# CC2538_MCU.net
KiCad netlist of a schematic drawn in Altium Designer
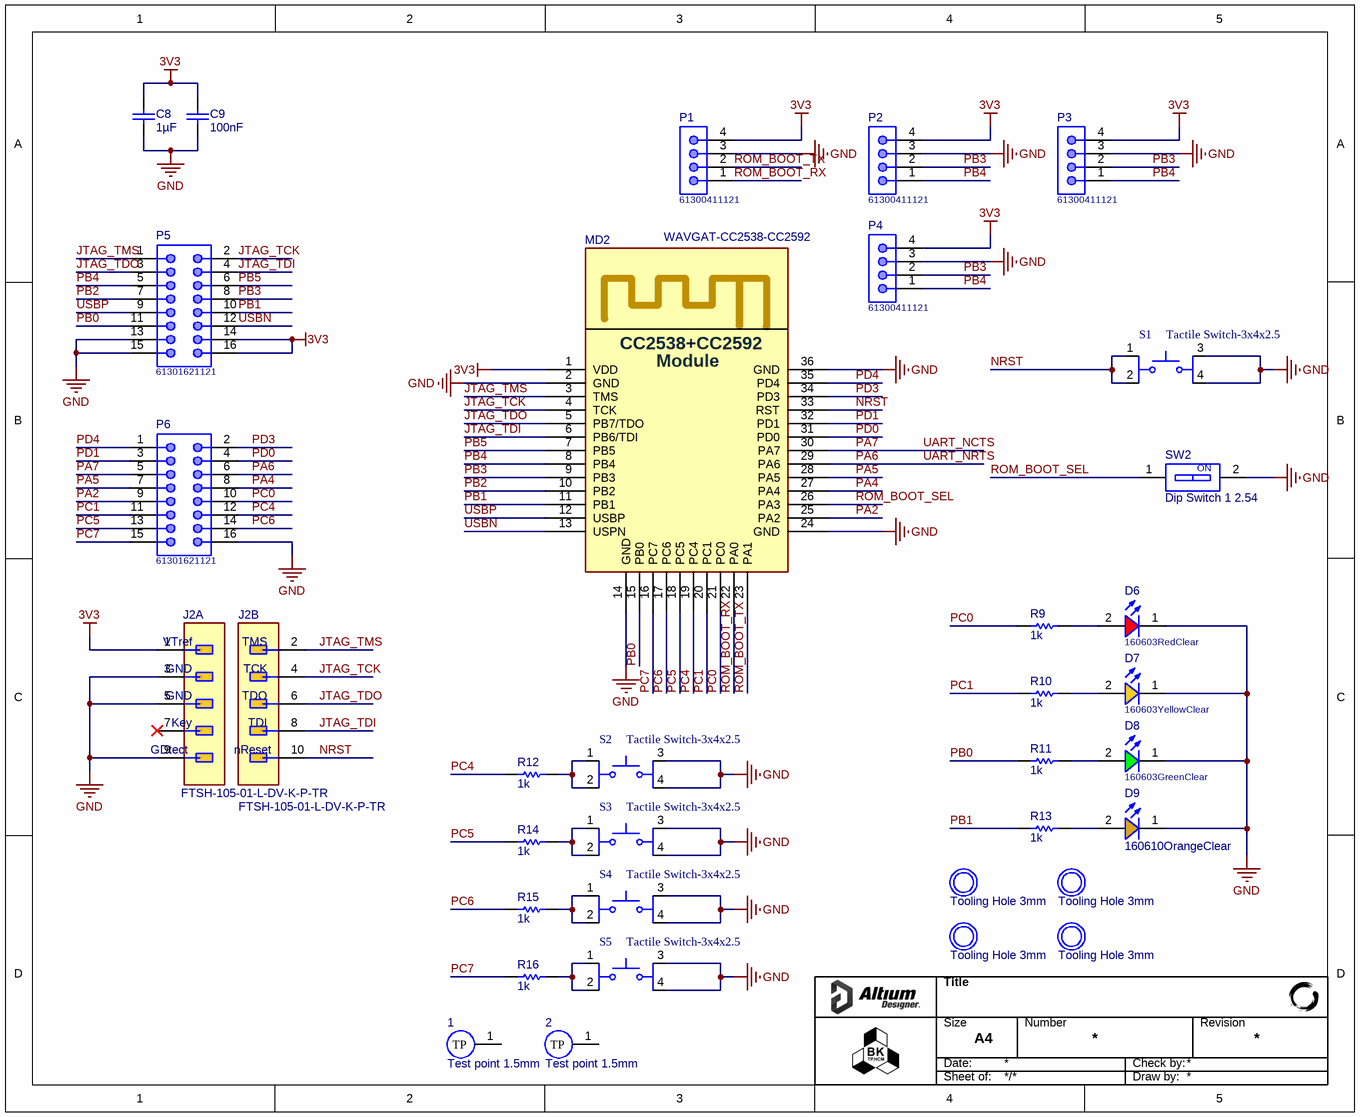
[diagram p0: [CC2538] MCU.SchDoc]

(export (version "E")
  (design (tool "Eeschema 10.0.6"))
  (components
    (comp (ref "1")
      (value "Test point 1.5mm")
      (footprint "Test point 1.5mm-Footprint-1")
      (description "Test point, 1.5mm radius")
      (libsource (lib "University of Technology") (part "TP"))
    )
    (comp (ref "2")
      (value "Test point 1.5mm")
      (footprint "Test point 1.5mm-Footprint-1")
      (description "Test point, 1.5mm radius")
      (libsource (lib "University of Technology") (part "TP"))
    )
    (comp (ref "C8")
      (value "1µF")
      (footprint "CAP_0603")
      (description "CAP, size 0603, 1 uF, 16 VDC, 10%")
      (fields
        (field (name "MANUFACTURER PART NUMBER") "CL10B105KO8NNWC")
        (field (name "TOLERANCE") "10%")
        (field (name "SOURCE") "Capacitor_0603_10_percent.SchLib")
      )
      (libsource (lib "University of Technology") (part "010603475106.3"))
    )
    (comp (ref "C9")
      (value "100nF")
      (footprint "CAP_0603")
      (description "CAP, size 0603, 100 nF, 50 VDC, 10%")
      (fields
        (field (name "MANUFACTURER PART NUMBER") "CGA3E3X8R1H104K080AE")
        (field (name "LCSC PART #") "C14663")
        (field (name "SOURCE") "Capacitor_0603_10_percent.SchLib")
      )
      (libsource (lib "University of Technology") (part "010603475106.3"))
    )
    (comp (ref "D6")
      (value "160603RedClear")
      (footprint "WL-SMCW_0603_H=0.7mm")
      (description "WL-SMCW SMT Mono-color Chip LED Waterclear, size 0603, Red, 2V, 140deg")
      (libsource (lib "University of Technology") (part "160603RedClear"))
    )
    (comp (ref "D7")
      (value "160603YellowClear")
      (footprint "WL-SMCW_0603_H=0.7mm")
      (description "WL-SMCW SMT Mono-color Chip LED Waterclear, size 0603, Yellow, 2V, 140deg")
      (libsource (lib "University of Technology") (part "160603YellowClear"))
    )
    (comp (ref "D8")
      (value "160603GreenClear")
      (footprint "WL-SMCW_0603_H=0.7mm")
      (description "WL-SMCW SMT Mono-color Chip LED Waterclear, size 0603, Green, 3.2V, 140deg")
      (libsource (lib "University of Technology") (part "160603GreenClear"))
    )
    (comp (ref "D9")
      (value "160610OrangeClear")
      (footprint "WL-SMCW_0603_H=0.7mm")
      (libsource (lib "University of Technology") (part "160610OrangeClear"))
    )
    (comp (ref "H1")
      (value "Tooling Hole 3mm")
      (footprint "3mm")
      (libsource (lib "University of Technology") (part "Tooling Hole 5mm"))
    )
    (comp (ref "H2")
      (value "Tooling Hole 3mm")
      (footprint "3mm")
      (libsource (lib "University of Technology") (part "Tooling Hole 5mm"))
    )
    (comp (ref "H3")
      (value "Tooling Hole 3mm")
      (footprint "3mm")
      (libsource (lib "University of Technology") (part "Tooling Hole 5mm"))
    )
    (comp (ref "H4")
      (value "Tooling Hole 3mm")
      (footprint "3mm")
      (libsource (lib "University of Technology") (part "Tooling Hole 5mm"))
    )
    (comp (ref "J2")
      (value "FTSH-105-01-L-DV-K-P-TR")
      (footprint "FP-FTSH-105-01-L-DV-K-P-T-MFG")
      (libsource (lib "University of Technology") (part "544f42128f4185dcb88ce1ce9bf1982"))
    )
    (comp (ref "MD2")
      (value "WAVGAT-CC2538-CC2592")
      (footprint "WAVGAT-CC2538-CC2592-Footprint")
      (description "WAVGAT-CC2538-CC2592 Module")
      (libsource (lib "University of Technology") (part "WAVGAT-CC2538-CC2592-Symbol"))
    )
    (comp (ref "P1")
      (value "61300411121")
      (footprint "61300411121")
      (description "WR-PHD Pin Header, THT, pitch 2.54mm, Single Row, Vertical, 4p")
      (fields (field (name "MANUFACTURER") "Wurth Elektronik"))
      (libsource (lib "University of Technology") (part "61300411121"))
    )
    (comp (ref "P2")
      (value "61300411121")
      (footprint "61300411121")
      (description "WR-PHD Pin Header, THT, pitch 2.54mm, Single Row, Vertical, 4p")
      (fields (field (name "MANUFACTURER") "Wurth Elektronik"))
      (libsource (lib "University of Technology") (part "61300411121"))
    )
    (comp (ref "P3")
      (value "61300411121")
      (footprint "61300411121")
      (description "WR-PHD Pin Header, THT, pitch 2.54mm, Single Row, Vertical, 4p")
      (fields (field (name "MANUFACTURER") "Wurth Elektronik"))
      (libsource (lib "University of Technology") (part "61300411121"))
    )
    (comp (ref "P4")
      (value "61300411121")
      (footprint "61300411121")
      (description "WR-PHD Pin Header, THT, pitch 2.54mm, Single Row, Vertical, 4p")
      (fields (field (name "MANUFACTURER") "Wurth Elektronik"))
      (libsource (lib "University of Technology") (part "61300411121"))
    )
    (comp (ref "P5")
      (value "61301621121")
      (footprint "61301621121")
      (description "WR-PHD Pin Header, THT, pitch 2.54mm, Dual Row, Vertical, 16p")
      (fields (field (name "MANUFACTURER") "Wurth Elektronik"))
      (libsource (lib "University of Technology") (part "61301621121"))
    )
    (comp (ref "P6")
      (value "61301621121")
      (footprint "61301621121")
      (description "WR-PHD Pin Header, THT, pitch 2.54mm, Dual Row, Vertical, 16p")
      (fields (field (name "MANUFACTURER") "Wurth Elektronik"))
      (libsource (lib "University of Technology") (part "61301621121"))
    )
    (comp (ref "R9")
      (value "1k")
      (footprint "RES_0603")
      (description "RES, size 0603, 1 KOhm, 1/10 W, 1%")
      (fields (field (name "TOLERANCE") "1%") (field (name "MANUFACTURER PART NUMBER") "RC0603FR-071KL"))
      (libsource (lib "University of Technology") (part "00060371541"))
    )
    (comp (ref "R10")
      (value "1k")
      (footprint "RES_0603")
      (description "RES, size 0603, 1 KOhm, 1/10 W, 1%")
      (fields (field (name "TOLERANCE") "1%") (field (name "MANUFACTURER PART NUMBER") "RC0603FR-071KL"))
      (libsource (lib "University of Technology") (part "00060371541"))
    )
    (comp (ref "R11")
      (value "1k")
      (footprint "RES_0603")
      (description "RES, size 0603, 1 KOhm, 1/10 W, 1%")
      (fields (field (name "TOLERANCE") "1%") (field (name "MANUFACTURER PART NUMBER") "RC0603FR-071KL"))
      (libsource (lib "University of Technology") (part "00060371541"))
    )
    (comp (ref "R12")
      (value "1k")
      (footprint "RES_0603")
      (description "RES, size 0603, 1 KOhm, 1/10 W, 5%")
      (fields (field (name "TOLERANCE") "5%") (field (name "MANUFACTURER PART NUMBER") "ERJ-UP3J102V"))
      (libsource (lib "University of Technology") (part "00060371541"))
    )
    (comp (ref "R13")
      (value "1k")
      (footprint "RES_0603")
      (description "RES, size 0603, 1 KOhm, 1/10 W, 1%")
      (fields (field (name "TOLERANCE") "1%") (field (name "MANUFACTURER PART NUMBER") "RC0603FR-071KL"))
      (libsource (lib "University of Technology") (part "00060371541"))
    )
    (comp (ref "R14")
      (value "1k")
      (footprint "RES_0603")
      (description "RES, size 0603, 1 KOhm, 1/10 W, 5%")
      (fields (field (name "TOLERANCE") "5%") (field (name "MANUFACTURER PART NUMBER") "ERJ-UP3J102V"))
      (libsource (lib "University of Technology") (part "00060371541"))
    )
    (comp (ref "R15")
      (value "1k")
      (footprint "RES_0603")
      (description "RES, size 0603, 1 KOhm, 1/10 W, 5%")
      (fields (field (name "TOLERANCE") "5%") (field (name "MANUFACTURER PART NUMBER") "ERJ-UP3J102V"))
      (libsource (lib "University of Technology") (part "00060371541"))
    )
    (comp (ref "R16")
      (value "1k")
      (footprint "RES_0603")
      (description "RES, size 0603, 1 KOhm, 1/10 W, 5%")
      (fields (field (name "TOLERANCE") "5%") (field (name "MANUFACTURER PART NUMBER") "ERJ-UP3J102V"))
      (libsource (lib "University of Technology") (part "00060371541"))
    )
    (comp (ref "S1")
      (value "Tactile Switch-3x4x2.5")
      (footprint "Tactile Switch-3x4x2.5 Footprint")
      (description "Tactile Switch, 3x4x2.5mm")
      (libsource (lib "University of Technology") (part "Tactile Switch"))
    )
    (comp (ref "S2")
      (value "Tactile Switch-3x4x2.5")
      (footprint "Tactile Switch-3x4x2.5 Footprint")
      (description "Tactile Switch, 3x4x2.5mm")
      (libsource (lib "University of Technology") (part "Tactile Switch"))
    )
    (comp (ref "S3")
      (value "Tactile Switch-3x4x2.5")
      (footprint "Tactile Switch-3x4x2.5 Footprint")
      (description "Tactile Switch, 3x4x2.5mm")
      (libsource (lib "University of Technology") (part "Tactile Switch"))
    )
    (comp (ref "S4")
      (value "Tactile Switch-3x4x2.5")
      (footprint "Tactile Switch-3x4x2.5 Footprint")
      (description "Tactile Switch, 3x4x2.5mm")
      (libsource (lib "University of Technology") (part "Tactile Switch"))
    )
    (comp (ref "S5")
      (value "Tactile Switch-3x4x2.5")
      (footprint "Tactile Switch-3x4x2.5 Footprint")
      (description "Tactile Switch, 3x4x2.5mm")
      (libsource (lib "University of Technology") (part "Tactile Switch"))
    )
    (comp (ref "SW2")
      (value "Dip Switch 1 2.54")
      (footprint "Dip Switch 1 2.54-Footprint-1")
      (libsource (lib "University of Technology") (part "Dip Switch 1 2.54-Symbol-1"))
    )
  )
  (nets
    (net (code "1") (name "/JTAG_TCK") (class "Default")
      (node (ref "J2") (pin "4") (pinfunction "3_4") (pintype "passive"))
      (node (ref "MD2") (pin "4") (pinfunction "TCK_4") (pintype "passive"))
      (node (ref "P5") (pin "2") (pinfunction "2_2") (pintype "passive"))
    )
    (net (code "2") (name "/JTAG_TDI") (class "Default")
      (node (ref "J2") (pin "8") (pinfunction "7_8") (pintype "passive"))
      (node (ref "MD2") (pin "6") (pinfunction "PB6/TDI_6") (pintype "passive"))
      (node (ref "P5") (pin "4") (pinfunction "4_4") (pintype "passive"))
    )
    (net (code "3") (name "/JTAG_TDO") (class "Default")
      (node (ref "J2") (pin "6") (pinfunction "5_6") (pintype "passive"))
      (node (ref "MD2") (pin "5") (pinfunction "PB7/TDO_5") (pintype "passive"))
      (node (ref "P5") (pin "3") (pinfunction "3_3") (pintype "passive"))
    )
    (net (code "4") (name "/JTAG_TMS") (class "Default")
      (node (ref "J2") (pin "2") (pinfunction "VTref_2") (pintype "passive"))
      (node (ref "MD2") (pin "3") (pinfunction "TMS_3") (pintype "passive"))
      (node (ref "P5") (pin "1") (pinfunction "1_1") (pintype "passive"))
    )
    (net (code "5") (name "/NRST") (class "Default")
      (node (ref "J2") (pin "10") (pinfunction "9_10") (pintype "passive"))
      (node (ref "MD2") (pin "33") (pinfunction "RST_33") (pintype "passive"))
      (node (ref "S1") (pin "1") (pinfunction "1_1") (pintype "passive"))
      (node (ref "S1") (pin "2") (pinfunction "2_2") (pintype "passive"))
    )
    (net (code "6") (name "/PA2") (class "Default")
      (node (ref "MD2") (pin "25") (pinfunction "PA2_25") (pintype "passive"))
      (node (ref "P6") (pin "9") (pinfunction "9_9") (pintype "passive"))
    )
    (net (code "7") (name "/PA4") (class "Default")
      (node (ref "MD2") (pin "27") (pinfunction "PA4_27") (pintype "passive"))
      (node (ref "P6") (pin "8") (pinfunction "8_8") (pintype "passive"))
    )
    (net (code "8") (name "/PA5") (class "Default")
      (node (ref "MD2") (pin "28") (pinfunction "PA5_28") (pintype "passive"))
      (node (ref "P6") (pin "7") (pinfunction "7_7") (pintype "passive"))
    )
    (net (code "9") (name "/PA6") (class "Default")
      (node (ref "MD2") (pin "29") (pinfunction "PA6_29") (pintype "passive"))
      (node (ref "P6") (pin "6") (pinfunction "6_6") (pintype "passive"))
    )
    (net (code "10") (name "/PA7") (class "Default")
      (node (ref "MD2") (pin "30") (pinfunction "PA7_30") (pintype "passive"))
      (node (ref "P6") (pin "5") (pinfunction "5_5") (pintype "passive"))
    )
    (net (code "11") (name "/PB0") (class "Default")
      (node (ref "MD2") (pin "15") (pinfunction "PB0_15") (pintype "passive"))
      (node (ref "P5") (pin "11") (pinfunction "11_11") (pintype "passive"))
      (node (ref "R11") (pin "1") (pinfunction "1_1") (pintype "passive"))
    )
    (net (code "12") (name "/PB1") (class "Default")
      (node (ref "MD2") (pin "11") (pinfunction "PB1_11") (pintype "passive"))
      (node (ref "P5") (pin "10") (pinfunction "10_10") (pintype "passive"))
      (node (ref "R13") (pin "1") (pinfunction "1_1") (pintype "passive"))
    )
    (net (code "13") (name "/PB2") (class "Default")
      (node (ref "MD2") (pin "10") (pinfunction "PB2_10") (pintype "passive"))
      (node (ref "P5") (pin "7") (pinfunction "7_7") (pintype "passive"))
    )
    (net (code "14") (name "/PB3") (class "Default")
      (node (ref "MD2") (pin "9") (pinfunction "PB3_9") (pintype "passive"))
      (node (ref "P2") (pin "2") (pinfunction "2_2") (pintype "passive"))
      (node (ref "P3") (pin "2") (pinfunction "2_2") (pintype "passive"))
      (node (ref "P4") (pin "2") (pinfunction "2_2") (pintype "passive"))
      (node (ref "P5") (pin "8") (pinfunction "8_8") (pintype "passive"))
    )
    (net (code "15") (name "/PB4") (class "Default")
      (node (ref "MD2") (pin "8") (pinfunction "PB4_8") (pintype "passive"))
      (node (ref "P2") (pin "1") (pinfunction "1_1") (pintype "passive"))
      (node (ref "P3") (pin "1") (pinfunction "1_1") (pintype "passive"))
      (node (ref "P4") (pin "1") (pinfunction "1_1") (pintype "passive"))
      (node (ref "P5") (pin "5") (pinfunction "5_5") (pintype "passive"))
    )
    (net (code "16") (name "/PB5") (class "Default")
      (node (ref "MD2") (pin "7") (pinfunction "PB5_7") (pintype "passive"))
      (node (ref "P5") (pin "6") (pinfunction "6_6") (pintype "passive"))
    )
    (net (code "17") (name "/PC0") (class "Default")
      (node (ref "MD2") (pin "21") (pinfunction "PC0_21") (pintype "passive"))
      (node (ref "P6") (pin "10") (pinfunction "10_10") (pintype "passive"))
      (node (ref "R9") (pin "1") (pinfunction "1_1") (pintype "passive"))
    )
    (net (code "18") (name "/PC1") (class "Default")
      (node (ref "MD2") (pin "20") (pinfunction "PC1_20") (pintype "passive"))
      (node (ref "P6") (pin "11") (pinfunction "11_11") (pintype "passive"))
      (node (ref "R10") (pin "1") (pinfunction "1_1") (pintype "passive"))
    )
    (net (code "19") (name "/PC4") (class "Default")
      (node (ref "MD2") (pin "19") (pinfunction "PC4_19") (pintype "passive"))
      (node (ref "P6") (pin "12") (pinfunction "12_12") (pintype "passive"))
      (node (ref "R12") (pin "1") (pinfunction "1_1") (pintype "passive"))
    )
    (net (code "20") (name "/PC5") (class "Default")
      (node (ref "MD2") (pin "18") (pinfunction "PC5_18") (pintype "passive"))
      (node (ref "P6") (pin "13") (pinfunction "13_13") (pintype "passive"))
      (node (ref "R14") (pin "1") (pinfunction "1_1") (pintype "passive"))
    )
    (net (code "21") (name "/PC6") (class "Default")
      (node (ref "MD2") (pin "17") (pinfunction "PC6_17") (pintype "passive"))
      (node (ref "P6") (pin "14") (pinfunction "14_14") (pintype "passive"))
      (node (ref "R15") (pin "1") (pinfunction "1_1") (pintype "passive"))
    )
    (net (code "22") (name "/PC7") (class "Default")
      (node (ref "MD2") (pin "16") (pinfunction "PC7_16") (pintype "passive"))
      (node (ref "P6") (pin "15") (pinfunction "15_15") (pintype "passive"))
      (node (ref "R16") (pin "1") (pinfunction "1_1") (pintype "passive"))
    )
    (net (code "23") (name "/PD0") (class "Default")
      (node (ref "MD2") (pin "31") (pinfunction "PD0_31") (pintype "passive"))
      (node (ref "P6") (pin "4") (pinfunction "4_4") (pintype "passive"))
    )
    (net (code "24") (name "/PD1") (class "Default")
      (node (ref "MD2") (pin "32") (pinfunction "PD1_32") (pintype "passive"))
      (node (ref "P6") (pin "3") (pinfunction "3_3") (pintype "passive"))
    )
    (net (code "25") (name "/PD3") (class "Default")
      (node (ref "MD2") (pin "34") (pinfunction "PD3_34") (pintype "passive"))
      (node (ref "P6") (pin "2") (pinfunction "2_2") (pintype "passive"))
    )
    (net (code "26") (name "/PD4") (class "Default")
      (node (ref "MD2") (pin "35") (pinfunction "PD4_35") (pintype "passive"))
      (node (ref "P6") (pin "1") (pinfunction "1_1") (pintype "passive"))
    )
    (net (code "27") (name "/ROM_BOOT_RX") (class "Default")
      (node (ref "MD2") (pin "22") (pinfunction "PA0_22") (pintype "passive"))
      (node (ref "P1") (pin "1") (pinfunction "1_1") (pintype "passive"))
    )
    (net (code "28") (name "/ROM_BOOT_SEL") (class "Default")
      (node (ref "MD2") (pin "26") (pinfunction "PA3_26") (pintype "passive"))
      (node (ref "SW2") (pin "1") (pinfunction "1_1") (pintype "passive"))
    )
    (net (code "29") (name "/ROM_BOOT_TX") (class "Default")
      (node (ref "MD2") (pin "23") (pinfunction "PA1_23") (pintype "passive"))
      (node (ref "P1") (pin "2") (pinfunction "2_2") (pintype "passive"))
    )
    (net (code "30") (name "/USBN") (class "Default")
      (node (ref "MD2") (pin "13") (pinfunction "USPN_13") (pintype "passive"))
      (node (ref "P5") (pin "12") (pinfunction "12_12") (pintype "passive"))
    )
    (net (code "31") (name "/USBP") (class "Default")
      (node (ref "MD2") (pin "12") (pinfunction "USBP_12") (pintype "passive"))
      (node (ref "P5") (pin "9") (pinfunction "9_9") (pintype "passive"))
    )
    (net (code "32") (name "3V3") (class "Default")
      (node (ref "C8") (pin "2") (pinfunction "2_2") (pintype "passive"))
      (node (ref "C9") (pin "2") (pinfunction "2_2") (pintype "passive"))
      (node (ref "J2") (pin "1") (pinfunction "VTref_1") (pintype "passive"))
      (node (ref "MD2") (pin "1") (pinfunction "VDD_1") (pintype "power_in"))
      (node (ref "P1") (pin "4") (pinfunction "4_4") (pintype "passive"))
      (node (ref "P2") (pin "4") (pinfunction "4_4") (pintype "passive"))
      (node (ref "P3") (pin "4") (pinfunction "4_4") (pintype "passive"))
      (node (ref "P4") (pin "4") (pinfunction "4_4") (pintype "passive"))
      (node (ref "P5") (pin "14") (pinfunction "14_14") (pintype "passive"))
      (node (ref "P5") (pin "16") (pinfunction "16_16") (pintype "passive"))
    )
    (net (code "33") (name "GND") (class "Default")
      (node (ref "C8") (pin "1") (pinfunction "1_1") (pintype "passive"))
      (node (ref "C9") (pin "1") (pinfunction "1_1") (pintype "passive"))
      (node (ref "D6") (pin "1") (pinfunction "K_1") (pintype "passive"))
      (node (ref "D7") (pin "1") (pinfunction "K_1") (pintype "passive"))
      (node (ref "D8") (pin "1") (pinfunction "K_1") (pintype "passive"))
      (node (ref "D9") (pin "1") (pinfunction "K_1") (pintype "passive"))
      (node (ref "J2") (pin "3") (pinfunction "3_3") (pintype "passive"))
      (node (ref "J2") (pin "5") (pinfunction "5_5") (pintype "passive"))
      (node (ref "J2") (pin "9") (pinfunction "9_9") (pintype "passive"))
      (node (ref "MD2") (pin "14") (pinfunction "GND_14") (pintype "power_in"))
      (node (ref "MD2") (pin "2") (pinfunction "GND_2") (pintype "power_in"))
      (node (ref "MD2") (pin "24") (pinfunction "GND_24") (pintype "passive"))
      (node (ref "MD2") (pin "36") (pinfunction "GND_36") (pintype "passive"))
      (node (ref "P1") (pin "3") (pinfunction "3_3") (pintype "passive"))
      (node (ref "P2") (pin "3") (pinfunction "3_3") (pintype "passive"))
      (node (ref "P3") (pin "3") (pinfunction "3_3") (pintype "passive"))
      (node (ref "P4") (pin "3") (pinfunction "3_3") (pintype "passive"))
      (node (ref "P5") (pin "13") (pinfunction "13_13") (pintype "passive"))
      (node (ref "P5") (pin "15") (pinfunction "15_15") (pintype "passive"))
      (node (ref "P6") (pin "16") (pinfunction "16_16") (pintype "passive"))
      (node (ref "S1") (pin "3") (pinfunction "3_3") (pintype "passive"))
      (node (ref "S1") (pin "4") (pinfunction "4_4") (pintype "passive"))
      (node (ref "S2") (pin "3") (pinfunction "3_3") (pintype "passive"))
      (node (ref "S2") (pin "4") (pinfunction "4_4") (pintype "passive"))
      (node (ref "S3") (pin "3") (pinfunction "3_3") (pintype "passive"))
      (node (ref "S3") (pin "4") (pinfunction "4_4") (pintype "passive"))
      (node (ref "S4") (pin "3") (pinfunction "3_3") (pintype "passive"))
      (node (ref "S4") (pin "4") (pinfunction "4_4") (pintype "passive"))
      (node (ref "S5") (pin "3") (pinfunction "3_3") (pintype "passive"))
      (node (ref "S5") (pin "4") (pinfunction "4_4") (pintype "passive"))
      (node (ref "SW2") (pin "2") (pinfunction "2_2") (pintype "passive"))
    )
    (net (code "34") (name "Net-(D6-A)") (class "Default")
      (node (ref "D6") (pin "2") (pinfunction "A_2") (pintype "passive"))
      (node (ref "R9") (pin "2") (pinfunction "2_2") (pintype "passive"))
    )
    (net (code "35") (name "Net-(D7-A)") (class "Default")
      (node (ref "D7") (pin "2") (pinfunction "A_2") (pintype "passive"))
      (node (ref "R10") (pin "2") (pinfunction "2_2") (pintype "passive"))
    )
    (net (code "36") (name "Net-(D8-A)") (class "Default")
      (node (ref "D8") (pin "2") (pinfunction "A_2") (pintype "passive"))
      (node (ref "R11") (pin "2") (pinfunction "2_2") (pintype "passive"))
    )
    (net (code "37") (name "Net-(D9-A)") (class "Default")
      (node (ref "D9") (pin "2") (pinfunction "A_2") (pintype "passive"))
      (node (ref "R13") (pin "2") (pinfunction "2_2") (pintype "passive"))
    )
    (net (code "38") (name "Net-(R12-Pad2)") (class "Default")
      (node (ref "R12") (pin "2") (pinfunction "2_2") (pintype "passive"))
      (node (ref "S2") (pin "1") (pinfunction "1_1") (pintype "passive"))
      (node (ref "S2") (pin "2") (pinfunction "2_2") (pintype "passive"))
    )
    (net (code "39") (name "Net-(R14-Pad2)") (class "Default")
      (node (ref "R14") (pin "2") (pinfunction "2_2") (pintype "passive"))
      (node (ref "S3") (pin "1") (pinfunction "1_1") (pintype "passive"))
      (node (ref "S3") (pin "2") (pinfunction "2_2") (pintype "passive"))
    )
    (net (code "40") (name "Net-(R15-Pad2)") (class "Default")
      (node (ref "R15") (pin "2") (pinfunction "2_2") (pintype "passive"))
      (node (ref "S4") (pin "1") (pinfunction "1_1") (pintype "passive"))
      (node (ref "S4") (pin "2") (pinfunction "2_2") (pintype "passive"))
    )
    (net (code "41") (name "Net-(R16-Pad2)") (class "Default")
      (node (ref "R16") (pin "2") (pinfunction "2_2") (pintype "passive"))
      (node (ref "S5") (pin "1") (pinfunction "1_1") (pintype "passive"))
      (node (ref "S5") (pin "2") (pinfunction "2_2") (pintype "passive"))
    )
    (net (code "42") (name "unconnected-(1-TP-Pad1)") (class "Default")
      (node (ref "1") (pin "1") (pinfunction "TP_1") (pintype "passive"))
    )
    (net (code "43") (name "unconnected-(2-TP-Pad1)") (class "Default")
      (node (ref "2") (pin "1") (pinfunction "TP_1") (pintype "passive"))
    )
    (net (code "44") (name "unconnected-(J2-Pad7)") (class "Default")
      (node (ref "J2") (pin "7") (pinfunction "7_7") (pintype "passive+no_connect"))
    )
  )
)
